# SOT223-SOT89.net
KiCad netlist of a schematic drawn in EAGLE
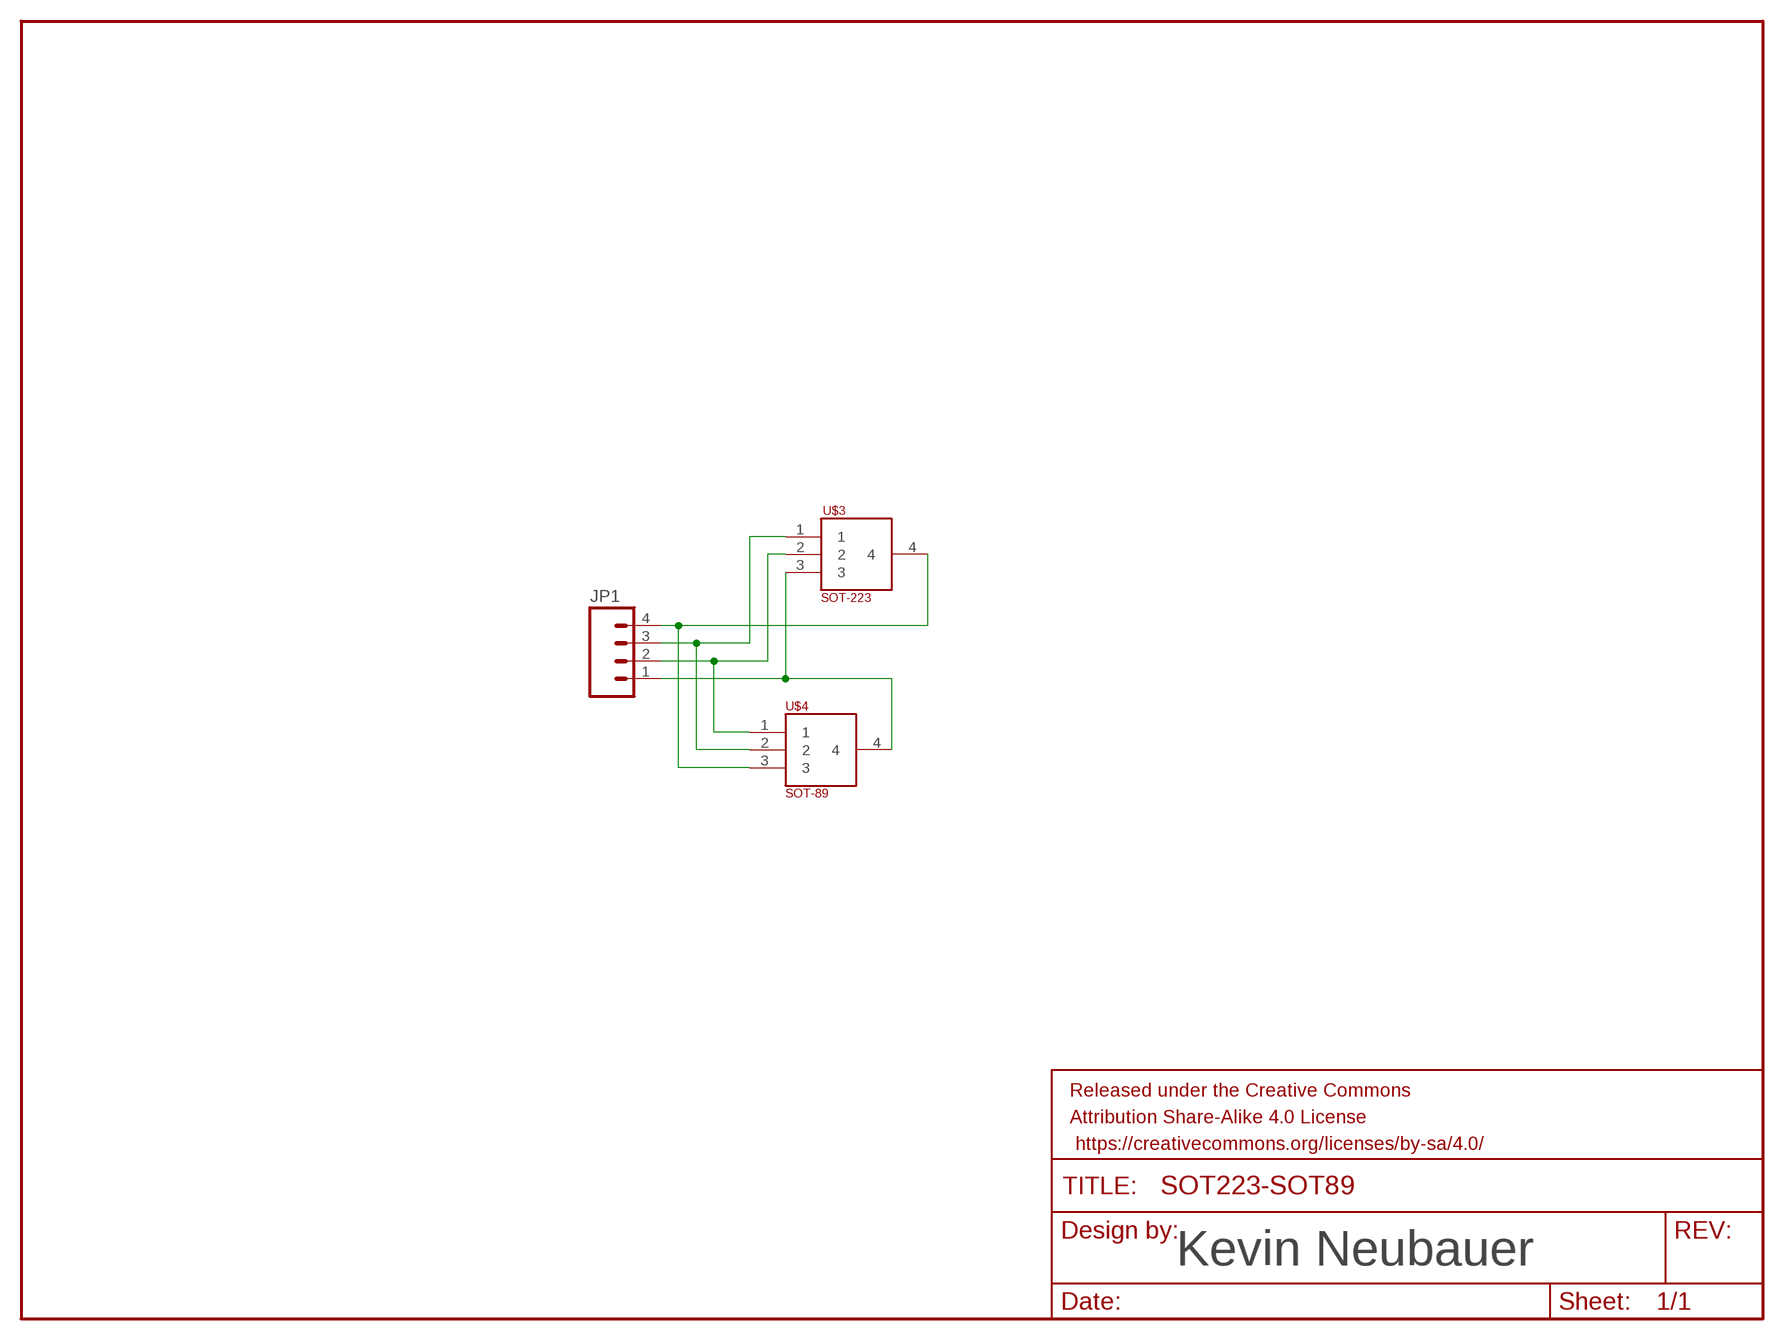
[diagram p0: schematic, sheet 1]

(export (version "E")
  (design (tool "Eeschema 10.0.6"))
  (components
    (comp (ref "FRAME1")
      (value "FRAME-LETTER")
      (footprint "eagle-import:CREATIVE_COMMONS")
      (libsource (lib "eagle-import") (part "FRAME-LETTER"))
    )
    (comp (ref "JP1")
      (value "M04PTH")
      (footprint "eagle-import:1X04")
      (libsource (lib "eagle-import") (part "M04PTH"))
    )
    (comp (ref "U$3")
      (value "SOT-223")
      (footprint "eagle-import:SOT-223")
      (libsource (lib "eagle-import") (part "SOT-223"))
    )
    (comp (ref "U$4")
      (value "SOT-89")
      (footprint "eagle-import:SOT-89")
      (libsource (lib "eagle-import") (part "SOT-89"))
    )
  )
  (nets
    (net (code "1") (name "Net-(JP1-Pad1)") (class "Default")
      (node (ref "JP1") (pin "1") (pinfunction "1_1") (pintype "passive"))
      (node (ref "U$3") (pin "3") (pinfunction "3_3") (pintype "bidirectional"))
      (node (ref "U$4") (pin "4") (pinfunction "4_4") (pintype "bidirectional"))
    )
    (net (code "2") (name "Net-(JP1-Pad2)") (class "Default")
      (node (ref "JP1") (pin "2") (pinfunction "2_2") (pintype "passive"))
      (node (ref "U$3") (pin "2") (pinfunction "2_2") (pintype "bidirectional"))
      (node (ref "U$4") (pin "1") (pinfunction "1_1") (pintype "bidirectional"))
    )
    (net (code "3") (name "Net-(JP1-Pad3)") (class "Default")
      (node (ref "JP1") (pin "3") (pinfunction "3_3") (pintype "passive"))
      (node (ref "U$3") (pin "1") (pinfunction "1_1") (pintype "bidirectional"))
      (node (ref "U$4") (pin "2") (pinfunction "2_2") (pintype "bidirectional"))
    )
    (net (code "4") (name "Net-(JP1-Pad4)") (class "Default")
      (node (ref "JP1") (pin "4") (pinfunction "4_4") (pintype "passive"))
      (node (ref "U$3") (pin "4") (pinfunction "4_4") (pintype "bidirectional"))
      (node (ref "U$4") (pin "3") (pinfunction "3_3") (pintype "bidirectional"))
    )
  )
)
